# Main.net
KiCad netlist of a schematic drawn in Altium Designer
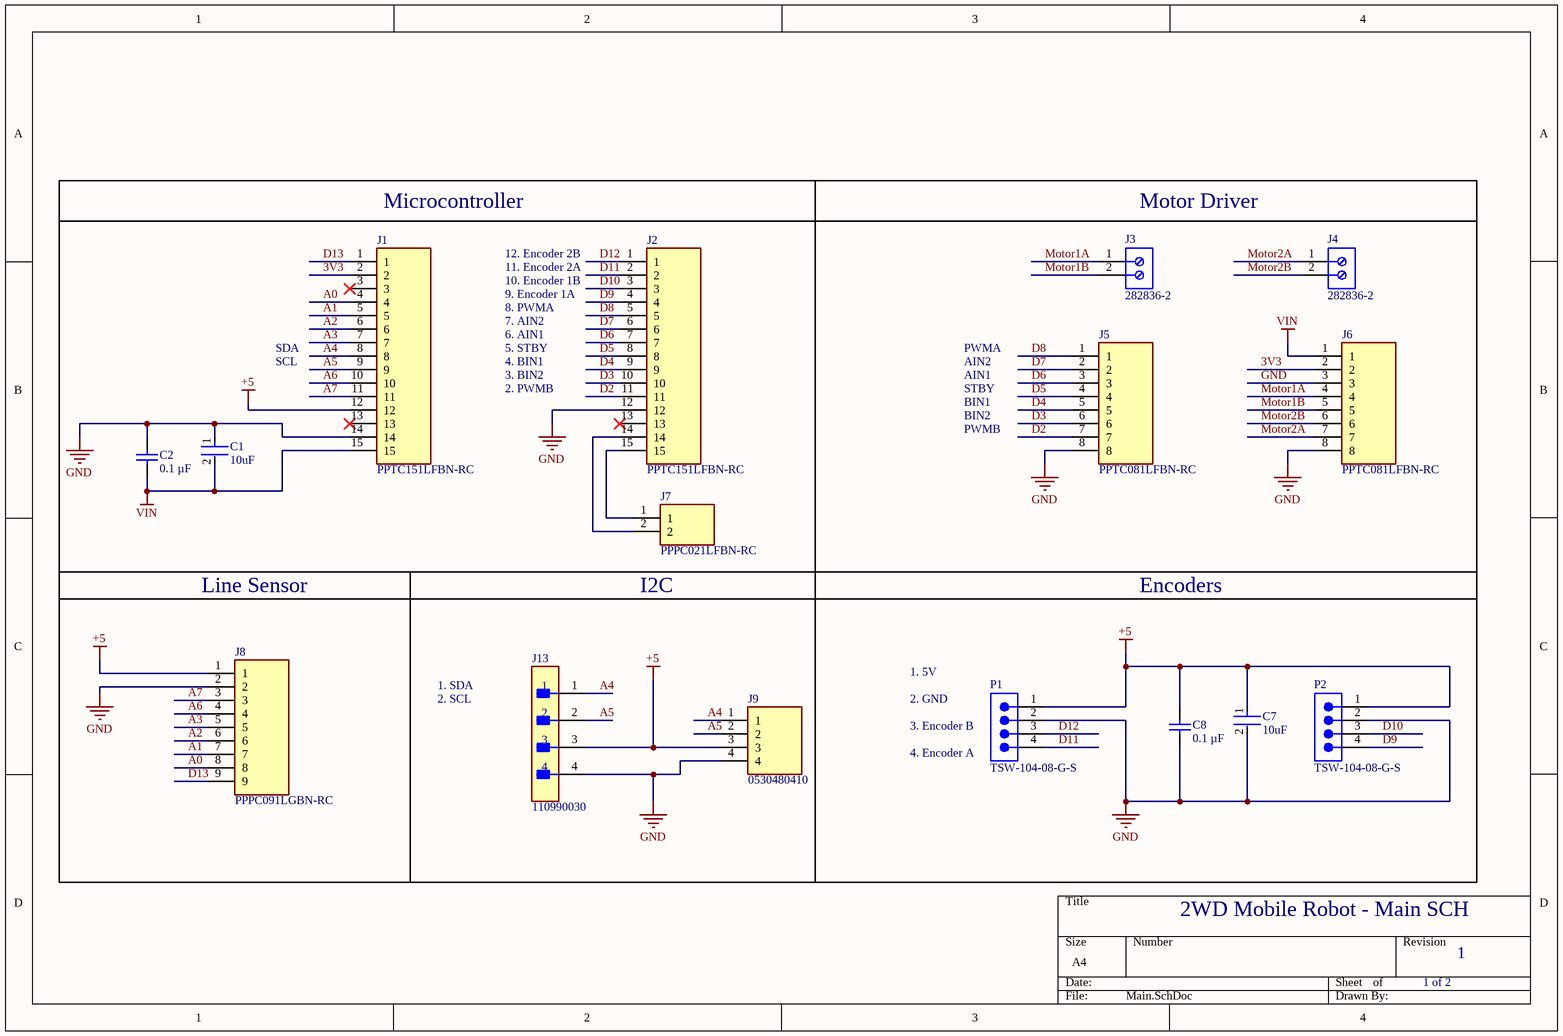
[diagram p0: Main.SchDoc]

(export (version "E")
  (design (tool "Eeschema 10.0.6"))
  (components
    (comp (ref "C1")
      (value "10uF")
      (footprint "FP-GRM21B-0_2-e0_2_0_7-IPC_C")
      (description "Chip Multilayer Ceramic Capacitors for General Purpose, 0805, 10uF, X5R, 15%, 10%, 35V")
      (fields (field (name "TOLERANCE") "10%"))
      (libsource (lib "Altium Content Vault") (part "b4654b650e69147ec39a6b967a45e02"))
    )
    (comp (ref "C2")
      (value "0.1 µF")
      (footprint "CAPC2013X140X50ML20T25")
      (description "0.1 µF ±10% 35V Ceramic Capacitor X5R 0805 (2012 Metric)")
      (fields
        (field (name "PART NUMBER") "0805DD104KAT2A")
        (field (name "MANUFACTURER") "AVX Interconnect / Elco")
      )
      (libsource (lib "Altium Content Vault") (part "CAP"))
    )
    (comp (ref "C7")
      (value "10uF")
      (footprint "FP-GRM21B-0_2-e0_2_0_7-IPC_C")
      (description "Chip Multilayer Ceramic Capacitors for General Purpose, 0805, 10uF, X5R, 15%, 10%, 35V")
      (fields (field (name "TOLERANCE") "10%"))
      (libsource (lib "Altium Content Vault") (part "b4654b650e69147ec39a6b967a45e02"))
    )
    (comp (ref "C8")
      (value "0.1 µF")
      (footprint "CAPC2013X140X50ML20T25")
      (description "0.1 µF ±10% 35V Ceramic Capacitor X5R 0805 (2012 Metric)")
      (fields
        (field (name "PART NUMBER") "0805DD104KAT2A")
        (field (name "MANUFACTURER") "AVX Interconnect / Elco")
      )
      (libsource (lib "Altium Content Vault") (part "CAP"))
    )
    (comp (ref "J1")
      (value "PPTC151LFBN-RC")
      (footprint "SamacSys:RHDR15W85P0X254_1X15_3708X254X850P")
      (description "Connector")
      (libsource (lib "*") (part "PPTC151LFBN-RC"))
    )
    (comp (ref "J2")
      (value "PPTC151LFBN-RC")
      (footprint "SamacSys:RHDR15W85P0X254_1X15_3708X254X850P")
      (description "Connector")
      (libsource (lib "*") (part "PPTC151LFBN-RC"))
    )
    (comp (ref "J3")
      (value "282836-2")
      (footprint "TECO-282836-2_V")
      (description "Female Header, Pitch 5 mm, 1 x 2 Position, Height 10 mm, Tail Length 3.5 mm, Rohs, Bulk")
      (fields (field (name "VOLTAGE") "300V") (field (name "MANUFACTURER") "TE Connectivity"))
      (libsource (lib "Altium Content Vault") (part "CN-1P-F-TB2"))
    )
    (comp (ref "J4")
      (value "282836-2")
      (footprint "TECO-282836-2_V")
      (description "Female Header, Pitch 5 mm, 1 x 2 Position, Height 10 mm, Tail Length 3.5 mm, Rohs, Bulk")
      (fields (field (name "VOLTAGE") "300V") (field (name "MANUFACTURER") "TE Connectivity"))
      (libsource (lib "Altium Content Vault") (part "CN-1P-F-TB2"))
    )
    (comp (ref "J5")
      (value "PPTC081LFBN-RC")
      (footprint "SamacSys:RHDR8W80P0X254_1X8_2082X254X850P")
      (description "Connector")
      (libsource (lib "*") (part "PPTC081LFBN-RC"))
    )
    (comp (ref "J6")
      (value "PPTC081LFBN-RC")
      (footprint "SamacSys:RHDR8W80P0X254_1X8_2082X254X850P")
      (description "Connector")
      (libsource (lib "*") (part "PPTC081LFBN-RC"))
    )
    (comp (ref "J7")
      (value "PPPC021LFBN-RC")
      (footprint "SamacSys:RHDR2W80P0X254_1X2_558X254X850P")
      (description "Connector")
      (libsource (lib "*") (part "PPPC021LFBN-RC"))
    )
    (comp (ref "J8")
      (value "PPPC091LGBN-RC")
      (footprint "SamacSys:RHDRRA9W60P0X254_1X9_2336X850X274P")
      (description "Connector")
      (libsource (lib "*") (part "PPPC091LGBN-RC"))
    )
    (comp (ref "J9")
      (value "0530480410")
      (footprint "SamacSys:SHDRRA4W35P0X125_1X4_675X550X350P")
      (description "Connector")
      (libsource (lib "*") (part "0530480410"))
    )
    (comp (ref "J13")
      (value "110990030")
      (footprint "FP-110990030-MFG")
      (description "GROVE 2MM 4PIN VERT CONN 10PCS")
      (libsource (lib "Altium Content Vault") (part "299a8cea1bdcbc3624fe62c390fa72c"))
    )
    (comp (ref "P1")
      (value "TSW-104-08-G-S")
      (footprint "SMTC-TSW-104-08-X-S")
      (description "0.025\" SQ Post Header, Through-hole, Vertical, -55 to 125 degC, 2.54 mm Pitch, 4-Pin, Male, RoHS")
      (fields (field (name "MANUFACTURER") "Samtec"))
      (libsource (lib "Altium Content Vault") (part "SMTC-TSW-104-08-X-S"))
    )
    (comp (ref "P2")
      (value "TSW-104-08-G-S")
      (footprint "SMTC-TSW-104-08-X-S")
      (description "0.025\" SQ Post Header, Through-hole, Vertical, -55 to 125 degC, 2.54 mm Pitch, 4-Pin, Male, RoHS")
      (fields (field (name "MANUFACTURER") "Samtec"))
      (libsource (lib "Altium Content Vault") (part "SMTC-TSW-104-08-X-S"))
    )
  )
  (nets
    (net (code "1") (name "+5") (class "Default")
      (node (ref "C7") (pin "1") (pinfunction "1_1") (pintype "passive"))
      (node (ref "C8") (pin "2") (pinfunction "2_2") (pintype "passive"))
      (node (ref "J1") (pin "12") (pinfunction "12_12") (pintype "passive"))
      (node (ref "J13") (pin "3") (pinfunction "3_3") (pintype "passive"))
      (node (ref "J8") (pin "1") (pinfunction "1_1") (pintype "passive"))
      (node (ref "J9") (pin "3") (pinfunction "3_3") (pintype "passive"))
      (node (ref "P1") (pin "1") (pinfunction "1_1") (pintype "passive"))
      (node (ref "P2") (pin "1") (pinfunction "1_1") (pintype "passive"))
    )
    (net (code "2") (name "/3V3") (class "Default")
      (node (ref "J1") (pin "2") (pinfunction "2_2") (pintype "passive"))
      (node (ref "J6") (pin "2") (pinfunction "2_2") (pintype "passive"))
    )
    (net (code "3") (name "/A0") (class "Default")
      (node (ref "J1") (pin "4") (pinfunction "4_4") (pintype "passive"))
      (node (ref "J8") (pin "8") (pinfunction "8_8") (pintype "passive"))
    )
    (net (code "4") (name "/A1") (class "Default")
      (node (ref "J1") (pin "5") (pinfunction "5_5") (pintype "passive"))
      (node (ref "J8") (pin "7") (pinfunction "7_7") (pintype "passive"))
    )
    (net (code "5") (name "/A2") (class "Default")
      (node (ref "J1") (pin "6") (pinfunction "6_6") (pintype "passive"))
      (node (ref "J8") (pin "6") (pinfunction "6_6") (pintype "passive"))
    )
    (net (code "6") (name "/A3") (class "Default")
      (node (ref "J1") (pin "7") (pinfunction "7_7") (pintype "passive"))
      (node (ref "J8") (pin "5") (pinfunction "5_5") (pintype "passive"))
    )
    (net (code "7") (name "/A4") (class "Default")
      (node (ref "J1") (pin "8") (pinfunction "8_8") (pintype "passive"))
      (node (ref "J13") (pin "1") (pinfunction "1_1") (pintype "passive"))
      (node (ref "J9") (pin "1") (pinfunction "1_1") (pintype "passive"))
    )
    (net (code "8") (name "/A5") (class "Default")
      (node (ref "J1") (pin "9") (pinfunction "9_9") (pintype "passive"))
      (node (ref "J13") (pin "2") (pinfunction "2_2") (pintype "passive"))
      (node (ref "J9") (pin "2") (pinfunction "2_2") (pintype "passive"))
    )
    (net (code "9") (name "/A6") (class "Default")
      (node (ref "J1") (pin "10") (pinfunction "10_10") (pintype "passive"))
      (node (ref "J8") (pin "4") (pinfunction "4_4") (pintype "passive"))
    )
    (net (code "10") (name "/A7") (class "Default")
      (node (ref "J1") (pin "11") (pinfunction "11_11") (pintype "passive"))
      (node (ref "J8") (pin "3") (pinfunction "3_3") (pintype "passive"))
    )
    (net (code "11") (name "/D2") (class "Default")
      (node (ref "J2") (pin "11") (pinfunction "11_11") (pintype "passive"))
      (node (ref "J5") (pin "7") (pinfunction "7_7") (pintype "passive"))
    )
    (net (code "12") (name "/D3") (class "Default")
      (node (ref "J2") (pin "10") (pinfunction "10_10") (pintype "passive"))
      (node (ref "J5") (pin "6") (pinfunction "6_6") (pintype "passive"))
    )
    (net (code "13") (name "/D4") (class "Default")
      (node (ref "J2") (pin "9") (pinfunction "9_9") (pintype "passive"))
      (node (ref "J5") (pin "5") (pinfunction "5_5") (pintype "passive"))
    )
    (net (code "14") (name "/D5") (class "Default")
      (node (ref "J2") (pin "8") (pinfunction "8_8") (pintype "passive"))
      (node (ref "J5") (pin "4") (pinfunction "4_4") (pintype "passive"))
    )
    (net (code "15") (name "/D6") (class "Default")
      (node (ref "J2") (pin "7") (pinfunction "7_7") (pintype "passive"))
      (node (ref "J5") (pin "3") (pinfunction "3_3") (pintype "passive"))
    )
    (net (code "16") (name "/D7") (class "Default")
      (node (ref "J2") (pin "6") (pinfunction "6_6") (pintype "passive"))
      (node (ref "J5") (pin "2") (pinfunction "2_2") (pintype "passive"))
    )
    (net (code "17") (name "/D8") (class "Default")
      (node (ref "J2") (pin "5") (pinfunction "5_5") (pintype "passive"))
      (node (ref "J5") (pin "1") (pinfunction "1_1") (pintype "passive"))
    )
    (net (code "18") (name "/D9") (class "Default")
      (node (ref "J2") (pin "4") (pinfunction "4_4") (pintype "passive"))
      (node (ref "P2") (pin "4") (pinfunction "4_4") (pintype "passive"))
    )
    (net (code "19") (name "/D10") (class "Default")
      (node (ref "J2") (pin "3") (pinfunction "3_3") (pintype "passive"))
      (node (ref "P2") (pin "3") (pinfunction "3_3") (pintype "passive"))
    )
    (net (code "20") (name "/D11") (class "Default")
      (node (ref "J2") (pin "2") (pinfunction "2_2") (pintype "passive"))
      (node (ref "P1") (pin "4") (pinfunction "4_4") (pintype "passive"))
    )
    (net (code "21") (name "/D12") (class "Default")
      (node (ref "J2") (pin "1") (pinfunction "1_1") (pintype "passive"))
      (node (ref "P1") (pin "3") (pinfunction "3_3") (pintype "passive"))
    )
    (net (code "22") (name "/D13") (class "Default")
      (node (ref "J1") (pin "1") (pinfunction "1_1") (pintype "passive"))
      (node (ref "J8") (pin "9") (pinfunction "9_9") (pintype "passive"))
    )
    (net (code "23") (name "/Motor1A") (class "Default")
      (node (ref "J3") (pin "1") (pinfunction "1_1") (pintype "passive"))
      (node (ref "J6") (pin "4") (pinfunction "4_4") (pintype "passive"))
    )
    (net (code "24") (name "/Motor1B") (class "Default")
      (node (ref "J3") (pin "2") (pinfunction "2_2") (pintype "passive"))
      (node (ref "J6") (pin "5") (pinfunction "5_5") (pintype "passive"))
    )
    (net (code "25") (name "/Motor2A") (class "Default")
      (node (ref "J4") (pin "1") (pinfunction "1_1") (pintype "passive"))
      (node (ref "J6") (pin "7") (pinfunction "7_7") (pintype "passive"))
    )
    (net (code "26") (name "/Motor2B") (class "Default")
      (node (ref "J4") (pin "2") (pinfunction "2_2") (pintype "passive"))
      (node (ref "J6") (pin "6") (pinfunction "6_6") (pintype "passive"))
    )
    (net (code "27") (name "GND") (class "Default")
      (node (ref "C1") (pin "1") (pinfunction "1_1") (pintype "passive"))
      (node (ref "C2") (pin "2") (pinfunction "2_2") (pintype "passive"))
      (node (ref "C7") (pin "2") (pinfunction "2_2") (pintype "passive"))
      (node (ref "C8") (pin "1") (pinfunction "1_1") (pintype "passive"))
      (node (ref "J1") (pin "14") (pinfunction "14_14") (pintype "passive"))
      (node (ref "J13") (pin "4") (pinfunction "4_4") (pintype "passive"))
      (node (ref "J2") (pin "12") (pinfunction "12_12") (pintype "passive"))
      (node (ref "J5") (pin "8") (pinfunction "8_8") (pintype "passive"))
      (node (ref "J6") (pin "3") (pinfunction "3_3") (pintype "passive"))
      (node (ref "J6") (pin "8") (pinfunction "8_8") (pintype "passive"))
      (node (ref "J8") (pin "2") (pinfunction "2_2") (pintype "passive"))
      (node (ref "J9") (pin "4") (pinfunction "4_4") (pintype "passive"))
      (node (ref "P1") (pin "2") (pinfunction "2_2") (pintype "passive"))
      (node (ref "P2") (pin "2") (pinfunction "2_2") (pintype "passive"))
    )
    (net (code "28") (name "Net-(J2-Pad14)") (class "Default")
      (node (ref "J2") (pin "14") (pinfunction "14_14") (pintype "passive"))
      (node (ref "J7") (pin "2") (pinfunction "2_2") (pintype "passive"))
    )
    (net (code "29") (name "Net-(J2-Pad15)") (class "Default")
      (node (ref "J2") (pin "15") (pinfunction "15_15") (pintype "passive"))
      (node (ref "J7") (pin "1") (pinfunction "1_1") (pintype "passive"))
    )
    (net (code "30") (name "VIN") (class "Default")
      (node (ref "C1") (pin "2") (pinfunction "2_2") (pintype "passive"))
      (node (ref "C2") (pin "1") (pinfunction "1_1") (pintype "passive"))
      (node (ref "J1") (pin "15") (pinfunction "15_15") (pintype "passive"))
      (node (ref "J6") (pin "1") (pinfunction "1_1") (pintype "passive"))
    )
    (net (code "31") (name "unconnected-(J1-Pad3)") (class "Default")
      (node (ref "J1") (pin "3") (pinfunction "3_3") (pintype "passive+no_connect"))
    )
    (net (code "32") (name "unconnected-(J1-Pad13)") (class "Default")
      (node (ref "J1") (pin "13") (pinfunction "13_13") (pintype "passive+no_connect"))
    )
    (net (code "33") (name "unconnected-(J2-Pad13)") (class "Default")
      (node (ref "J2") (pin "13") (pinfunction "13_13") (pintype "passive+no_connect"))
    )
  )
)
